# voltage_selector_and_output.net
KiCad netlist of a schematic drawn in EAGLE
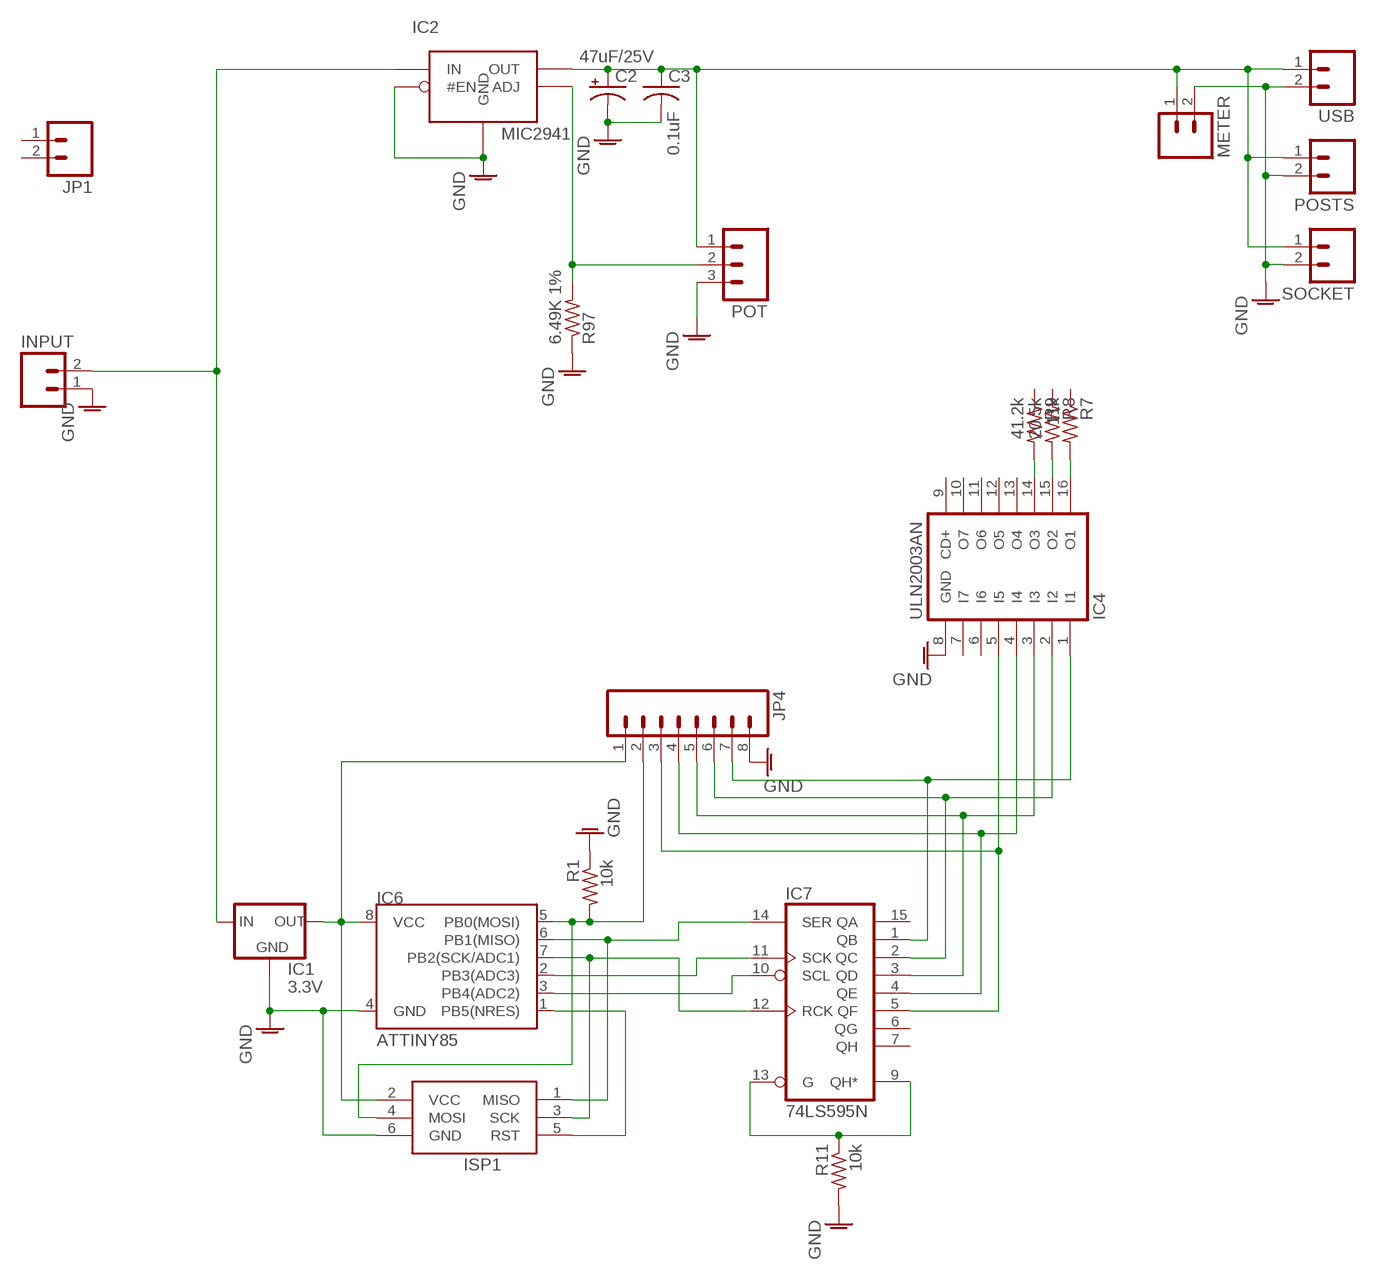
[diagram p0: schematic, sheet 1]

(export (version "E")
  (design (tool "Eeschema 10.0.6"))
  (components
    (comp (ref "C2")
      (value "47uF/25V")
      (footprint "eagle-import:E2,5-6")
      (libsource (lib "eagle-import") (part "CPOL-USE2.5-6"))
    )
    (comp (ref "C3")
      (value "0.1uF")
      (footprint "eagle-import:C025-025X050")
      (libsource (lib "eagle-import") (part "C-US025-025X050"))
    )
    (comp (ref "IC1")
      (value "3.3V")
      (footprint "eagle-import:78XXS")
      (libsource (lib "eagle-import") (part "78XXS"))
    )
    (comp (ref "IC2")
      (value "MIC2941")
      (footprint "eagle-import:TO220-5")
      (libsource (lib "eagle-import") (part "MIC2941"))
    )
    (comp (ref "IC4")
      (value "ULN2003AN")
      (footprint "eagle-import:DIL16")
      (libsource (lib "eagle-import") (part "ULN2003AN"))
    )
    (comp (ref "IC6")
      (value "ATTINY85")
      (footprint "eagle-import:DIP08")
      (libsource (lib "eagle-import") (part "ATTINY13DIP"))
    )
    (comp (ref "IC7")
      (value "74LS595N")
      (footprint "eagle-import:DIL16")
      (libsource (lib "eagle-import") (part "74595NLS"))
    )
    (comp (ref "INPUT")
      (value "M02PTH")
      (footprint "eagle-import:1X02")
      (libsource (lib "eagle-import") (part "M02PTH"))
    )
    (comp (ref "ISP1")
      (value "AVRISP-6")
      (footprint "eagle-import:AVRISP")
      (libsource (lib "eagle-import") (part "AVRISP-6"))
    )
    (comp (ref "JP1")
      (value "M02JST-PTH-2")
      (footprint "eagle-import:JST-2-PTH")
      (libsource (lib "eagle-import") (part "M02JST-PTH-2"))
    )
    (comp (ref "JP4")
      (value "M081X08")
      (footprint "eagle-import:1X08")
      (libsource (lib "eagle-import") (part "M081X08"))
    )
    (comp (ref "METER")
      (value "M02PTH")
      (footprint "eagle-import:1X02")
      (libsource (lib "eagle-import") (part "M02PTH"))
    )
    (comp (ref "POSTS")
      (value "M02PTH")
      (footprint "eagle-import:1X02")
      (libsource (lib "eagle-import") (part "M02PTH"))
    )
    (comp (ref "POT")
      (value "M03PTH")
      (footprint "eagle-import:1X03")
      (libsource (lib "eagle-import") (part "M03PTH"))
    )
    (comp (ref "R1")
      (value "10k")
      (footprint "eagle-import:0207_5V")
      (libsource (lib "eagle-import") (part "R-US_0207/5V"))
    )
    (comp (ref "R7")
      (value "11k")
      (footprint "eagle-import:0207_5V")
      (libsource (lib "eagle-import") (part "R-US_0207/5V"))
    )
    (comp (ref "R8")
      (value "20.5k")
      (footprint "eagle-import:0207_5V")
      (libsource (lib "eagle-import") (part "R-US_0207/5V"))
    )
    (comp (ref "R9")
      (value "41.2k")
      (footprint "eagle-import:0207_5V")
      (libsource (lib "eagle-import") (part "R-US_0207/5V"))
    )
    (comp (ref "R11")
      (value "10k")
      (footprint "eagle-import:0207_5V")
      (libsource (lib "eagle-import") (part "R-US_0207/5V"))
    )
    (comp (ref "R97")
      (value "6.49K 1%")
      (footprint "eagle-import:0207_5V")
      (libsource (lib "eagle-import") (part "R-US_0207/5V"))
    )
    (comp (ref "SOCKET")
      (value "M02PTH")
      (footprint "eagle-import:1X02")
      (libsource (lib "eagle-import") (part "M02PTH"))
    )
    (comp (ref "USB")
      (value "M02PTH")
      (footprint "eagle-import:1X02")
      (libsource (lib "eagle-import") (part "M02PTH"))
    )
  )
  (nets
    (net (code "1") (name "GND") (class "Default")
      (node (ref "C2") (pin "-") (pinfunction "-_-") (pintype "passive"))
      (node (ref "C3") (pin "2") (pinfunction "2_2") (pintype "passive"))
      (node (ref "IC1") (pin "GND") (pinfunction "GND_GND") (pintype "input"))
      (node (ref "IC2") (pin "2") (pinfunction "#EN_2") (pintype "input"))
      (node (ref "IC2") (pin "3") (pinfunction "GND_3") (pintype "input"))
      (node (ref "IC4") (pin "8") (pinfunction "GND_8") (pintype "power_in"))
      (node (ref "IC6") (pin "4") (pinfunction "GND_4") (pintype "bidirectional"))
      (node (ref "INPUT") (pin "1") (pinfunction "1_1") (pintype "passive"))
      (node (ref "ISP1") (pin "6") (pinfunction "GND_6") (pintype "power_in"))
      (node (ref "JP4") (pin "8") (pinfunction "8_8") (pintype "passive"))
      (node (ref "METER") (pin "2") (pinfunction "2_2") (pintype "passive"))
      (node (ref "POSTS") (pin "2") (pinfunction "2_2") (pintype "passive"))
      (node (ref "POT") (pin "3") (pinfunction "3_3") (pintype "passive"))
      (node (ref "R1") (pin "1") (pinfunction "1_1") (pintype "passive"))
      (node (ref "R11") (pin "2") (pinfunction "2_2") (pintype "passive"))
      (node (ref "R97") (pin "1") (pinfunction "1_1") (pintype "passive"))
      (node (ref "SOCKET") (pin "2") (pinfunction "2_2") (pintype "passive"))
      (node (ref "USB") (pin "2") (pinfunction "2_2") (pintype "passive"))
    )
    (net (code "2") (name "Net-(IC2-ADJ)") (class "Default")
      (node (ref "IC2") (pin "1") (pinfunction "ADJ_1") (pintype "input"))
      (node (ref "POT") (pin "2") (pinfunction "2_2") (pintype "passive"))
      (node (ref "R97") (pin "2") (pinfunction "2_2") (pintype "passive"))
    )
    (net (code "3") (name "Net-(IC2-IN)") (class "Default")
      (node (ref "IC1") (pin "IN") (pinfunction "IN_IN") (pintype "input"))
      (node (ref "IC2") (pin "4") (pinfunction "IN_4") (pintype "input"))
      (node (ref "INPUT") (pin "2") (pinfunction "2_2") (pintype "passive"))
    )
    (net (code "4") (name "Net-(IC2-OUT)") (class "Default")
      (node (ref "C2") (pin "+") (pinfunction "+_+") (pintype "passive"))
      (node (ref "C3") (pin "1") (pinfunction "1_1") (pintype "passive"))
      (node (ref "IC2") (pin "5") (pinfunction "OUT_5") (pintype "passive"))
      (node (ref "METER") (pin "1") (pinfunction "1_1") (pintype "passive"))
      (node (ref "POSTS") (pin "1") (pinfunction "1_1") (pintype "passive"))
      (node (ref "POT") (pin "1") (pinfunction "1_1") (pintype "passive"))
      (node (ref "SOCKET") (pin "1") (pinfunction "1_1") (pintype "passive"))
      (node (ref "USB") (pin "1") (pinfunction "1_1") (pintype "passive"))
    )
    (net (code "5") (name "Net-(IC4-I1)") (class "Default")
      (node (ref "IC4") (pin "1") (pinfunction "I1_1") (pintype "input"))
      (node (ref "IC7") (pin "1") (pinfunction "QB_1") (pintype "tri_state"))
      (node (ref "JP4") (pin "7") (pinfunction "7_7") (pintype "passive"))
    )
    (net (code "6") (name "Net-(IC4-I2)") (class "Default")
      (node (ref "IC4") (pin "2") (pinfunction "I2_2") (pintype "input"))
      (node (ref "IC7") (pin "2") (pinfunction "QC_2") (pintype "tri_state"))
      (node (ref "JP4") (pin "6") (pinfunction "6_6") (pintype "passive"))
    )
    (net (code "7") (name "Net-(IC4-I3)") (class "Default")
      (node (ref "IC4") (pin "3") (pinfunction "I3_3") (pintype "input"))
      (node (ref "IC7") (pin "3") (pinfunction "QD_3") (pintype "tri_state"))
      (node (ref "JP4") (pin "5") (pinfunction "5_5") (pintype "passive"))
    )
    (net (code "8") (name "Net-(IC4-I4)") (class "Default")
      (node (ref "IC4") (pin "4") (pinfunction "I4_4") (pintype "input"))
      (node (ref "IC7") (pin "4") (pinfunction "QE_4") (pintype "tri_state"))
      (node (ref "JP4") (pin "4") (pinfunction "4_4") (pintype "passive"))
    )
    (net (code "9") (name "Net-(IC4-I5)") (class "Default")
      (node (ref "IC4") (pin "5") (pinfunction "I5_5") (pintype "input"))
      (node (ref "IC7") (pin "5") (pinfunction "QF_5") (pintype "tri_state"))
      (node (ref "JP4") (pin "3") (pinfunction "3_3") (pintype "passive"))
    )
    (net (code "10") (name "Net-(IC4-O1)") (class "Default")
      (node (ref "IC4") (pin "16") (pinfunction "O1_16") (pintype "open_collector"))
      (node (ref "R7") (pin "2") (pinfunction "2_2") (pintype "passive"))
    )
    (net (code "11") (name "Net-(IC4-O2)") (class "Default")
      (node (ref "IC4") (pin "15") (pinfunction "O2_15") (pintype "open_collector"))
      (node (ref "R8") (pin "2") (pinfunction "2_2") (pintype "passive"))
    )
    (net (code "12") (name "Net-(IC4-O3)") (class "Default")
      (node (ref "IC4") (pin "14") (pinfunction "O3_14") (pintype "open_collector"))
      (node (ref "R9") (pin "2") (pinfunction "2_2") (pintype "passive"))
    )
    (net (code "13") (name "Net-(IC6-PB0(MOSI))") (class "Default")
      (node (ref "IC6") (pin "5") (pinfunction "PB0(MOSI)_5") (pintype "bidirectional"))
      (node (ref "ISP1") (pin "4") (pinfunction "MOSI_4") (pintype "output"))
      (node (ref "JP4") (pin "2") (pinfunction "2_2") (pintype "passive"))
      (node (ref "R1") (pin "2") (pinfunction "2_2") (pintype "passive"))
    )
    (net (code "14") (name "Net-(IC6-PB1(MISO))") (class "Default")
      (node (ref "IC6") (pin "6") (pinfunction "PB1(MISO)_6") (pintype "bidirectional"))
      (node (ref "IC7") (pin "14") (pinfunction "SER_14") (pintype "input"))
      (node (ref "ISP1") (pin "1") (pinfunction "MISO_1") (pintype "input"))
    )
    (net (code "15") (name "Net-(IC6-PB2(SCK{slash}ADC1))") (class "Default")
      (node (ref "IC6") (pin "7") (pinfunction "PB2(SCK/ADC1)_7") (pintype "bidirectional"))
      (node (ref "IC7") (pin "12") (pinfunction "RCK_12") (pintype "input"))
      (node (ref "ISP1") (pin "3") (pinfunction "SCK_3") (pintype "output"))
    )
    (net (code "16") (name "Net-(IC6-PB3(ADC3))") (class "Default")
      (node (ref "IC6") (pin "2") (pinfunction "PB3(ADC3)_2") (pintype "bidirectional"))
      (node (ref "IC7") (pin "11") (pinfunction "SCK_11") (pintype "input"))
    )
    (net (code "17") (name "Net-(IC6-PB4(ADC2))") (class "Default")
      (node (ref "IC6") (pin "3") (pinfunction "PB4(ADC2)_3") (pintype "bidirectional"))
      (node (ref "IC7") (pin "10") (pinfunction "SCL_10") (pintype "input"))
    )
    (net (code "18") (name "Net-(IC6-PB5(NRES))") (class "Default")
      (node (ref "IC6") (pin "1") (pinfunction "PB5(NRES)_1") (pintype "bidirectional"))
      (node (ref "ISP1") (pin "5") (pinfunction "RST_5") (pintype "output"))
    )
    (net (code "19") (name "Net-(IC6-VCC)") (class "Default")
      (node (ref "IC1") (pin "OUT") (pinfunction "OUT_OUT") (pintype "passive"))
      (node (ref "IC6") (pin "8") (pinfunction "VCC_8") (pintype "bidirectional"))
      (node (ref "ISP1") (pin "2") (pinfunction "VCC_2") (pintype "power_in"))
      (node (ref "JP4") (pin "1") (pinfunction "1_1") (pintype "passive"))
    )
    (net (code "20") (name "Net-(IC7A-G)") (class "Default")
      (node (ref "IC7") (pin "13") (pinfunction "G_13") (pintype "input"))
      (node (ref "IC7") (pin "9") (pinfunction "QH*_9") (pintype "tri_state"))
      (node (ref "R11") (pin "1") (pinfunction "1_1") (pintype "passive"))
    )
    (net (code "21") (name "unconnected-(IC4-CD+-Pad9)") (class "Default")
      (node (ref "IC4") (pin "9") (pinfunction "CD+_9") (pintype "passive"))
    )
    (net (code "22") (name "unconnected-(IC4-I6-Pad6)") (class "Default")
      (node (ref "IC4") (pin "6") (pinfunction "I6_6") (pintype "input"))
    )
    (net (code "23") (name "unconnected-(IC4-I7-Pad7)") (class "Default")
      (node (ref "IC4") (pin "7") (pinfunction "I7_7") (pintype "input"))
    )
    (net (code "24") (name "unconnected-(IC4-O4-Pad13)") (class "Default")
      (node (ref "IC4") (pin "13") (pinfunction "O4_13") (pintype "open_collector"))
    )
    (net (code "25") (name "unconnected-(IC4-O5-Pad12)") (class "Default")
      (node (ref "IC4") (pin "12") (pinfunction "O5_12") (pintype "open_collector"))
    )
    (net (code "26") (name "unconnected-(IC4-O6-Pad11)") (class "Default")
      (node (ref "IC4") (pin "11") (pinfunction "O6_11") (pintype "open_collector"))
    )
    (net (code "27") (name "unconnected-(IC4-O7-Pad10)") (class "Default")
      (node (ref "IC4") (pin "10") (pinfunction "O7_10") (pintype "open_collector"))
    )
    (net (code "28") (name "unconnected-(IC7A-QA-Pad15)") (class "Default")
      (node (ref "IC7") (pin "15") (pinfunction "QA_15") (pintype "tri_state"))
    )
    (net (code "29") (name "unconnected-(IC7A-QG-Pad6)") (class "Default")
      (node (ref "IC7") (pin "6") (pinfunction "QG_6") (pintype "tri_state"))
    )
    (net (code "30") (name "unconnected-(IC7A-QH-Pad7)") (class "Default")
      (node (ref "IC7") (pin "7") (pinfunction "QH_7") (pintype "tri_state"))
    )
    (net (code "31") (name "unconnected-(JP1-Pad1)") (class "Default")
      (node (ref "JP1") (pin "1") (pinfunction "1_1") (pintype "passive"))
    )
    (net (code "32") (name "unconnected-(JP1-Pad2)") (class "Default")
      (node (ref "JP1") (pin "2") (pinfunction "2_2") (pintype "passive"))
    )
    (net (code "33") (name "unconnected-(R7-Pad1)") (class "Default")
      (node (ref "R7") (pin "1") (pinfunction "1_1") (pintype "passive"))
    )
    (net (code "34") (name "unconnected-(R8-Pad1)") (class "Default")
      (node (ref "R8") (pin "1") (pinfunction "1_1") (pintype "passive"))
    )
    (net (code "35") (name "unconnected-(R9-Pad1)") (class "Default")
      (node (ref "R9") (pin "1") (pinfunction "1_1") (pintype "passive"))
    )
  )
)
